# LM399.net
KiCad netlist of a schematic drawn in Altium Designer
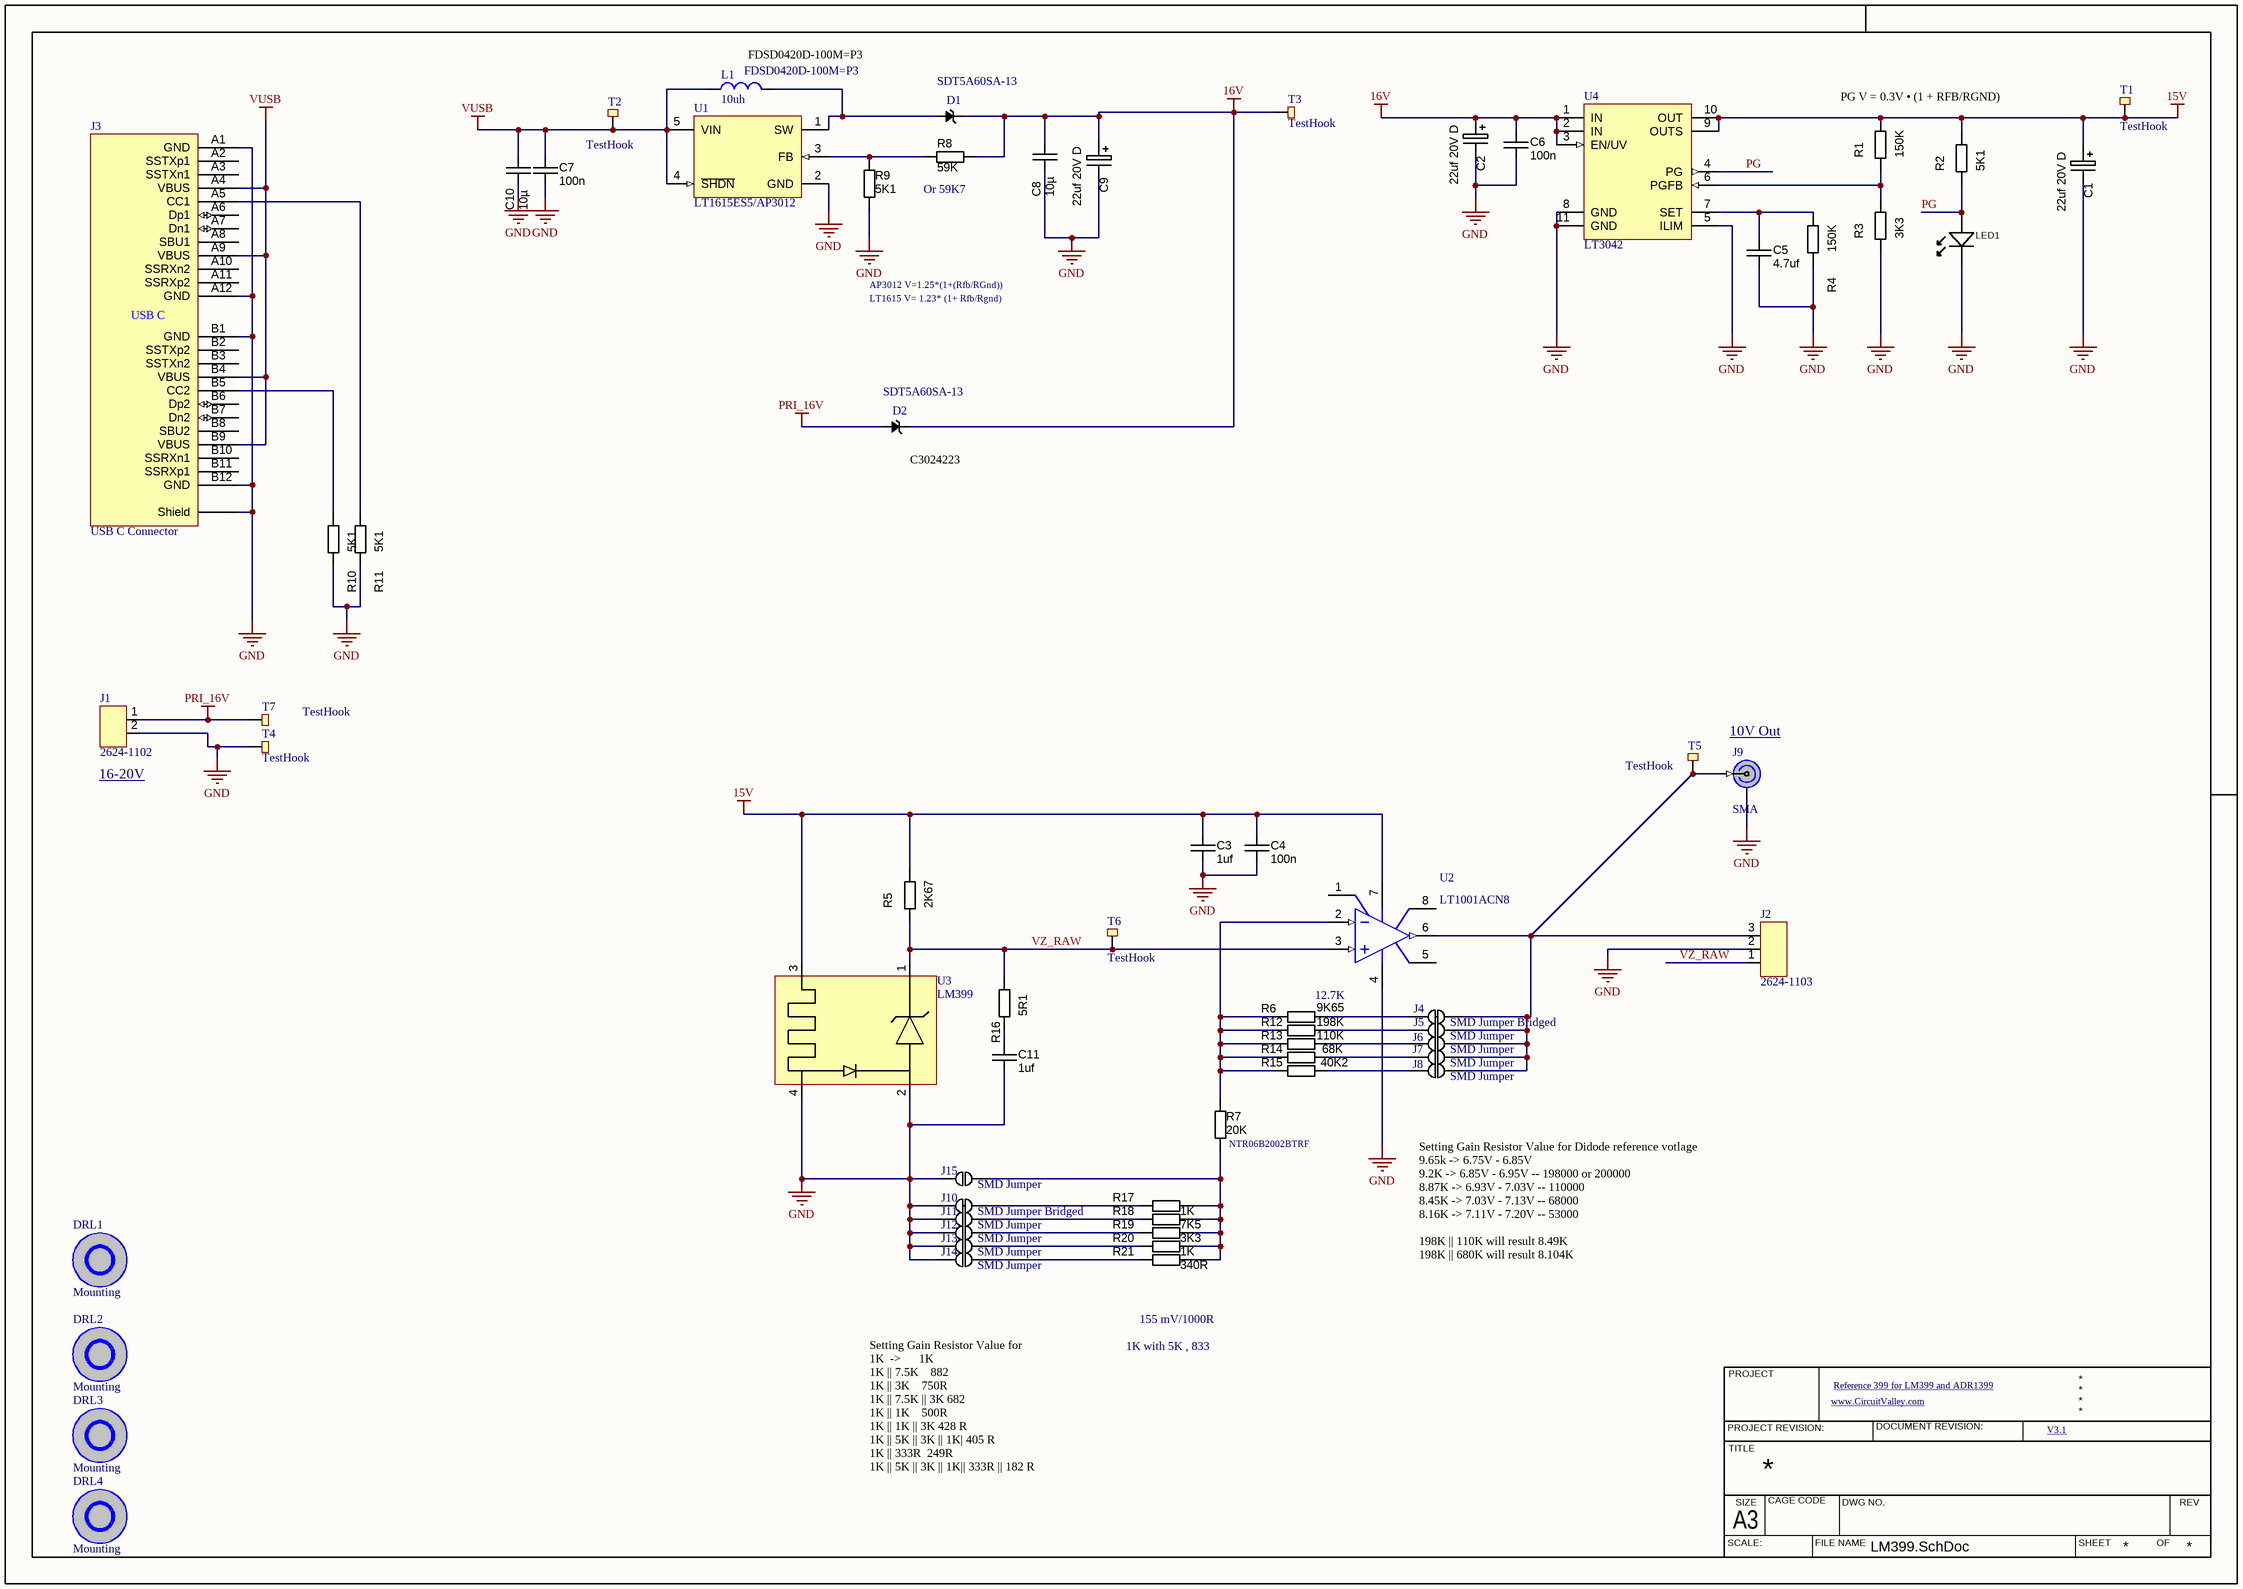
[diagram p0: LM399.SchDoc]

(export (version "E")
  (design (tool "Eeschema 10.0.6"))
  (components
    (comp (ref "C1")
      (value "22uf 20V D")
      (footprint "CAPMP7343X310N")
      (description "Capacitor SMD Tant 330uF 20% 6V3 2917")
      (fields
        (field (name "TOLERANCE") "±20%")
        (field (name "MANUFACTURER PART NUMBER") "T520D337M006ATE015")
      )
      (libsource (lib "PBL - Capacitors") (part "CAPT_330u_2917_6V3"))
    )
    (comp (ref "C2")
      (value "22uf 20V D")
      (footprint "CAPMP7343X310N")
      (description "Capacitor SMD Tant 330uF 20% 6V3 2917")
      (fields
        (field (name "TOLERANCE") "±20%")
        (field (name "MANUFACTURER PART NUMBER") "T520D337M006ATE015")
      )
      (libsource (lib "PBL - Capacitors") (part "CAPT_330u_2917_6V3"))
    )
    (comp (ref "C3")
      (value "1uf")
      (footprint "CAPC1608N")
      (description "Capacitor SMD Cer 1nF 10% 100V X7R 0603")
      (fields (field (name "TOLERANCE") "±10%") (field (name "Comment") "approved sub OK"))
      (libsource (lib "PBL - Capacitors") (part "CAPC_1n_0603_100V"))
    )
    (comp (ref "C4")
      (value "100n")
      (footprint "CAPC1608N")
      (description "Capacitor SMD Cer 1nF 10% 100V X7R 0603")
      (fields (field (name "TOLERANCE") "±10%") (field (name "Comment") "approved sub OK"))
      (libsource (lib "PBL - Capacitors") (part "CAPC_1n_0603_100V"))
    )
    (comp (ref "C5")
      (value "4.7uf")
      (footprint "CAPC1608N")
      (description "Capacitor SMD Cer 1nF 10% 100V X7R 0603")
      (fields (field (name "TOLERANCE") "±10%") (field (name "Comment") "approved sub OK"))
      (libsource (lib "PBL - Capacitors") (part "CAPC_1n_0603_100V"))
    )
    (comp (ref "C6")
      (value "100n")
      (footprint "CAPC1608N")
      (description "Capacitor SMD Cer 1nF 10% 100V X7R 0603")
      (fields (field (name "TOLERANCE") "±10%") (field (name "Comment") "approved sub OK"))
      (libsource (lib "PBL - Capacitors") (part "CAPC_1n_0603_100V"))
    )
    (comp (ref "C7")
      (value "100n")
      (footprint "CAPC1608N")
      (description "Capacitor SMD Cer 1nF 10% 100V X7R 0603")
      (fields (field (name "TOLERANCE") "±10%") (field (name "Comment") "approved sub OK"))
      (libsource (lib "PBL - Capacitors") (part "CAPC_1n_0603_100V"))
    )
    (comp (ref "C8")
      (value "10µ")
      (footprint "CAPC3225N")
      (description "Capacitor SMD Cer 10uF 20% 16V X5R 1210")
      (fields (field (name "TOLERANCE") "±20%"))
      (libsource (lib "PBL - Capacitors") (part "CAPC_10u_1210_50V"))
    )
    (comp (ref "C9")
      (value "22uf 20V D")
      (footprint "CAPMP7343X310N")
      (description "Capacitor SMD Tant 330uF 20% 6V3 2917")
      (fields
        (field (name "TOLERANCE") "±20%")
        (field (name "MANUFACTURER PART NUMBER") "T520D337M006ATE015")
      )
      (libsource (lib "PBL - Capacitors") (part "CAPT_330u_2917_6V3"))
    )
    (comp (ref "C10")
      (value "10µ")
      (footprint "CAPC3225N")
      (description "Capacitor SMD Cer 10uF 20% 16V X5R 1210")
      (fields (field (name "TOLERANCE") "±20%"))
      (libsource (lib "PBL - Capacitors") (part "CAPC_10u_1210_50V"))
    )
    (comp (ref "C11")
      (value "1uf")
      (footprint "CAPC1608N")
      (description "Capacitor SMD Cer 1nF 10% 100V X7R 0603")
      (fields (field (name "TOLERANCE") "±10%") (field (name "Comment") "approved sub OK"))
      (libsource (lib "PBL - Capacitors") (part "CAPC_1n_0603_100V"))
    )
    (comp (ref "D1")
      (value "SDT5A60SA-13")
      (footprint "DO-214AC")
      (libsource (lib "cvlib") (part "Schottky_diode"))
    )
    (comp (ref "D2")
      (value "SDT5A60SA-13")
      (footprint "DO-214AC")
      (libsource (lib "cvlib") (part "Schottky_diode"))
    )
    (comp (ref "DRL1")
      (value "Mounting")
      (footprint "NO_COPPER_NOMASK_2m75_6m2")
      (description "Mounting Hole")
      (libsource (lib "cvlib") (part "Mountinghole"))
    )
    (comp (ref "DRL2")
      (value "Mounting")
      (footprint "NO_COPPER_NOMASK_2m75_6m2")
      (description "Mounting Hole")
      (libsource (lib "cvlib") (part "Mountinghole"))
    )
    (comp (ref "DRL3")
      (value "Mounting")
      (footprint "NO_COPPER_NOMASK_2m75_6m2")
      (description "Mounting Hole")
      (libsource (lib "cvlib") (part "Mountinghole"))
    )
    (comp (ref "DRL4")
      (value "Mounting")
      (footprint "NO_COPPER_NOMASK_2m75_6m2")
      (description "Mounting Hole")
      (libsource (lib "cvlib") (part "Mountinghole"))
    )
    (comp (ref "J1") (value "2624-1102") (footprint "2624-1102") (libsource (lib "cvlib") (part "2624-1102")))
    (comp (ref "J2") (value "2624-1103") (footprint "2624-1103") (libsource (lib "cvlib") (part "2624-1103")))
    (comp (ref "J3")
      (value "USB C Connector")
      (footprint "UT11113-11602-7H")
      (description "USB C connector")
      (libsource (lib "cvlib") (part "USB_C"))
    )
    (comp (ref "J4")
      (value "SMD Jumper Bridged")
      (footprint "SMD_Jumper_bridge")
      (description "SMD Jumper")
      (libsource (lib "cvlib") (part "SMD_Jumper_Bridged"))
    )
    (comp (ref "J5")
      (value "SMD Jumper")
      (footprint "SMD_Jumper")
      (libsource (lib "cvlib") (part "SMD_Jumper"))
    )
    (comp (ref "J6")
      (value "SMD Jumper")
      (footprint "SMD_Jumper")
      (libsource (lib "cvlib") (part "SMD_Jumper"))
    )
    (comp (ref "J7")
      (value "SMD Jumper")
      (footprint "SMD_Jumper")
      (libsource (lib "cvlib") (part "SMD_Jumper"))
    )
    (comp (ref "J8")
      (value "SMD Jumper")
      (footprint "SMD_Jumper")
      (libsource (lib "cvlib") (part "SMD_Jumper"))
    )
    (comp (ref "J9")
      (value "SMA")
      (footprint "SMA_Connector")
      (libsource (lib "cvlib") (part "SMA Connector"))
    )
    (comp (ref "J10")
      (value "SMD Jumper Bridged")
      (footprint "SMD_Jumper_bridge")
      (description "SMD Jumper")
      (libsource (lib "cvlib") (part "SMD_Jumper_Bridged"))
    )
    (comp (ref "J11")
      (value "SMD Jumper")
      (footprint "SMD_Jumper")
      (libsource (lib "cvlib") (part "SMD_Jumper"))
    )
    (comp (ref "J12")
      (value "SMD Jumper")
      (footprint "SMD_Jumper")
      (libsource (lib "cvlib") (part "SMD_Jumper"))
    )
    (comp (ref "J13")
      (value "SMD Jumper")
      (footprint "SMD_Jumper")
      (libsource (lib "cvlib") (part "SMD_Jumper"))
    )
    (comp (ref "J14")
      (value "SMD Jumper")
      (footprint "SMD_Jumper")
      (libsource (lib "cvlib") (part "SMD_Jumper"))
    )
    (comp (ref "J15")
      (value "SMD Jumper")
      (footprint "SMD_Jumper")
      (libsource (lib "cvlib") (part "SMD_Jumper"))
    )
    (comp (ref "L1")
      (value "10uh")
      (footprint "FDSD0420-H-2R2M")
      (fields (field (name "ALTIUM_VALUE") "FDSD0420D-100M=P3"))
      (libsource (lib "cvlib") (part "inductor_smd"))
    )
    (comp (ref "LED1")
      (value "~")
      (footprint "LED-0805-K")
      (description "LED, 0805 SMD, Green")
      (libsource (lib "PBL - Light Sources") (part "LED_SMD_Green_0805"))
    )
    (comp (ref "R1")
      (value "150K")
      (footprint "RESC1608N")
      (description "Resistor, SMD chip")
      (fields (field (name "TOLERANCE") "±5%") (field (name "Comment") "RES_NL_0603"))
      (libsource (lib "PBL - Resistors") (part "RES_NL_0603"))
    )
    (comp (ref "R2")
      (value "5K1")
      (footprint "RESC1608N")
      (description "Resistor, SMD chip")
      (fields (field (name "TOLERANCE") "±5%") (field (name "Comment") "RES_NL_0603"))
      (libsource (lib "PBL - Resistors") (part "RES_NL_0603"))
    )
    (comp (ref "R3")
      (value "3K3")
      (footprint "RESC1608N")
      (description "Resistor, SMD chip")
      (fields (field (name "TOLERANCE") "±5%") (field (name "Comment") "RES_NL_0603"))
      (libsource (lib "PBL - Resistors") (part "RES_NL_0603"))
    )
    (comp (ref "R4")
      (value "150K")
      (footprint "RESC1608N")
      (description "Resistor, SMD chip")
      (fields (field (name "TOLERANCE") "±5%") (field (name "Comment") "RES_NL_0603"))
      (libsource (lib "PBL - Resistors") (part "RES_NL_0603"))
    )
    (comp (ref "R5")
      (value "2K67")
      (footprint "RESC1608N")
      (description "Resistor, SMD chip")
      (fields (field (name "TOLERANCE") "±5%") (field (name "Comment") "RES_NL_0603"))
      (libsource (lib "PBL - Resistors") (part "RES_NL_0603"))
    )
    (comp (ref "R6")
      (value "9K65")
      (footprint "RESC1608N")
      (description "Resistor, SMD chip")
      (fields (field (name "TOLERANCE") "±5%") (field (name "Comment") "RES_NL_0603"))
      (libsource (lib "") (part "RES_NL_0603_1"))
    )
    (comp (ref "R7")
      (value "20K")
      (footprint "RESC1608N")
      (description "Resistor, SMD chip")
      (fields (field (name "TOLERANCE") "±5%") (field (name "Comment") "RES_NL_0603"))
      (libsource (lib "PBL - Resistors") (part "RES_NL_0603"))
    )
    (comp (ref "R8")
      (value "59K")
      (footprint "RESC1608N")
      (description "Resistor, SMD chip")
      (fields (field (name "TOLERANCE") "±5%") (field (name "Comment") "RES_NL_0603"))
      (libsource (lib "") (part "RES_NL_0603_1"))
    )
    (comp (ref "R9")
      (value "5K1")
      (footprint "RESC1608N")
      (description "Resistor, SMD chip")
      (fields (field (name "TOLERANCE") "±5%") (field (name "Comment") "RES_NL_0603"))
      (libsource (lib "") (part "RES_NL_0603_3"))
    )
    (comp (ref "R10")
      (value "5K1")
      (footprint "RESC1608N")
      (description "Resistor, SMD chip")
      (fields (field (name "TOLERANCE") "±5%") (field (name "Comment") "RES_NL_0603"))
      (libsource (lib "PBL - Resistors") (part "RES_NL_0603"))
    )
    (comp (ref "R11")
      (value "5K1")
      (footprint "RESC1608N")
      (description "Resistor, SMD chip")
      (fields (field (name "TOLERANCE") "±5%") (field (name "Comment") "RES_NL_0603"))
      (libsource (lib "PBL - Resistors") (part "RES_NL_0603"))
    )
    (comp (ref "R12")
      (value "198K")
      (footprint "RESC1608N")
      (description "Resistor, SMD chip")
      (fields (field (name "TOLERANCE") "±5%") (field (name "Comment") "RES_NL_0603"))
      (libsource (lib "") (part "RES_NL_0603_1"))
    )
    (comp (ref "R13")
      (value "110K")
      (footprint "RESC1608N")
      (description "Resistor, SMD chip")
      (fields (field (name "TOLERANCE") "±5%") (field (name "Comment") "RES_NL_0603"))
      (libsource (lib "") (part "RES_NL_0603_1"))
    )
    (comp (ref "R14")
      (value "68K")
      (footprint "RESC1608N")
      (description "Resistor, SMD chip")
      (fields (field (name "TOLERANCE") "±5%") (field (name "Comment") "RES_NL_0603"))
      (libsource (lib "") (part "RES_NL_0603_1"))
    )
    (comp (ref "R15")
      (value "40K2")
      (footprint "RESC1608N")
      (description "Resistor, SMD chip")
      (fields (field (name "TOLERANCE") "±5%") (field (name "Comment") "RES_NL_0603"))
      (libsource (lib "") (part "RES_NL_0603_1"))
    )
    (comp (ref "R16")
      (value "5R1")
      (footprint "RESC1608N")
      (description "Resistor, SMD chip")
      (fields (field (name "TOLERANCE") "±5%") (field (name "Comment") "RES_NL_0603"))
      (libsource (lib "PBL - Resistors") (part "RES_NL_0603"))
    )
    (comp (ref "R17")
      (value "1K")
      (footprint "RESC1608N")
      (description "Resistor, SMD chip")
      (fields (field (name "TOLERANCE") "±5%") (field (name "Comment") "RES_NL_0603"))
      (libsource (lib "") (part "RES_NL_0603_2"))
    )
    (comp (ref "R18")
      (value "7K5")
      (footprint "RESC1608N")
      (description "Resistor, SMD chip")
      (fields (field (name "TOLERANCE") "±5%") (field (name "Comment") "RES_NL_0603"))
      (libsource (lib "") (part "RES_NL_0603_2"))
    )
    (comp (ref "R19")
      (value "3K3")
      (footprint "RESC1608N")
      (description "Resistor, SMD chip")
      (fields (field (name "TOLERANCE") "±5%") (field (name "Comment") "RES_NL_0603"))
      (libsource (lib "") (part "RES_NL_0603_2"))
    )
    (comp (ref "R20")
      (value "1K")
      (footprint "RESC1608N")
      (description "Resistor, SMD chip")
      (fields (field (name "TOLERANCE") "±5%") (field (name "Comment") "RES_NL_0603"))
      (libsource (lib "") (part "RES_NL_0603_2"))
    )
    (comp (ref "R21")
      (value "340R")
      (footprint "RESC1608N")
      (description "Resistor, SMD chip")
      (fields (field (name "TOLERANCE") "±5%") (field (name "Comment") "RES_NL_0603"))
      (libsource (lib "") (part "RES_NL_0603_2"))
    )
    (comp (ref "T1")
      (value "TestHook")
      (footprint "Test_PAD_0851-0-15-20-82-14-11-0")
      (libsource (lib "cvlib") (part "TestHook"))
    )
    (comp (ref "T2")
      (value "TestHook")
      (footprint "Test_PAD_0851-0-15-20-82-14-11-0")
      (libsource (lib "cvlib") (part "TestHook"))
    )
    (comp (ref "T3")
      (value "TestHook")
      (footprint "Test_PAD_0851-0-15-20-82-14-11-0")
      (libsource (lib "") (part "TestHook_1"))
    )
    (comp (ref "T4")
      (value "TestHook")
      (footprint "Test_PAD_0851-0-15-20-82-14-11-0")
      (libsource (lib "") (part "TestHook_1"))
    )
    (comp (ref "T5")
      (value "TestHook")
      (footprint "Test_PAD_0851-0-15-20-82-14-11-0")
      (libsource (lib "cvlib") (part "TestHook"))
    )
    (comp (ref "T6")
      (value "TestHook")
      (footprint "Test_PAD_0851-0-15-20-82-14-11-0")
      (libsource (lib "cvlib") (part "TestHook"))
    )
    (comp (ref "T7")
      (value "TestHook")
      (footprint "Test_PAD_0851-0-15-20-82-14-11-0")
      (libsource (lib "") (part "TestHook_1"))
    )
    (comp (ref "U1")
      (value "LT1615ES5/AP3012")
      (footprint "SOT23-5")
      (description "Boost Conveter")
      (libsource (lib "cvlib") (part "AP3012"))
    )
    (comp (ref "U2")
      (value "LT1001ACN8")
      (footprint "N8")
      (description "General Purpose, High Precision Op Amp")
      (fields (field (name "PUBLISHER") "Altium Limited"))
      (libsource (lib "LT Operational Amplifier") (part "LT1001ACN8"))
    )
    (comp (ref "U3") (value "LM399") (footprint "TO-46") (libsource (lib "cvlib") (part "LM399")))
    (comp (ref "U4")
      (value "LT3042")
      (footprint "MSOP10")
      (description "Low noise Linear Regulator")
      (libsource (lib "cvlib") (part "LT3042"))
    )
  )
  (nets
    (net (code "1") (name "/PG") (class "Default")
      (node (ref "LED1") (pin "A") (pinfunction "A_A") (pintype "passive"))
      (node (ref "R2") (pin "2") (pinfunction "2_2") (pintype "passive"))
      (node (ref "U4") (pin "4") (pinfunction "PG_4") (pintype "output"))
    )
    (net (code "2") (name "/VZ_RAW") (class "Default")
      (node (ref "J2") (pin "1") (pintype "passive"))
      (node (ref "R16") (pin "1") (pinfunction "1_1") (pintype "passive"))
      (node (ref "R5") (pin "2") (pinfunction "2_2") (pintype "passive"))
      (node (ref "T6") (pin "1") (pinfunction "TP_1") (pintype "power_in"))
      (node (ref "U2") (pin "3") (pinfunction "IN+_3") (pintype "input"))
      (node (ref "U3") (pin "1") (pinfunction "D1_1") (pintype "passive"))
    )
    (net (code "3") (name "15V") (class "Default")
      (node (ref "C1") (pin "1") (pintype "passive"))
      (node (ref "C3") (pin "1") (pintype "passive"))
      (node (ref "C4") (pin "1") (pintype "passive"))
      (node (ref "R1") (pin "1") (pinfunction "1_1") (pintype "passive"))
      (node (ref "R2") (pin "1") (pinfunction "1_1") (pintype "passive"))
      (node (ref "R5") (pin "1") (pinfunction "1_1") (pintype "passive"))
      (node (ref "T1") (pin "1") (pinfunction "TP_1") (pintype "power_in"))
      (node (ref "U2") (pin "7") (pinfunction "V+_7") (pintype "power_in"))
      (node (ref "U3") (pin "3") (pinfunction "H1_3") (pintype "passive"))
      (node (ref "U4") (pin "10") (pinfunction "OUT_10") (pintype "power_in"))
      (node (ref "U4") (pin "9") (pinfunction "OUTS_9") (pintype "passive"))
    )
    (net (code "4") (name "16V") (class "Default")
      (node (ref "C2") (pin "1") (pintype "passive"))
      (node (ref "C6") (pin "1") (pintype "passive"))
      (node (ref "C8") (pin "1") (pintype "passive"))
      (node (ref "C9") (pin "1") (pintype "passive"))
      (node (ref "D1") (pin "2") (pinfunction "2_2") (pintype "passive"))
      (node (ref "D2") (pin "2") (pinfunction "2_2") (pintype "passive"))
      (node (ref "R8") (pin "2") (pinfunction "2_2") (pintype "passive"))
      (node (ref "T3") (pin "1") (pinfunction "TP_1") (pintype "power_in"))
      (node (ref "U4") (pin "1") (pinfunction "IN_1") (pintype "power_in"))
      (node (ref "U4") (pin "2") (pinfunction "IN_2") (pintype "power_in"))
      (node (ref "U4") (pin "3") (pinfunction "EN/UV_3") (pintype "input"))
    )
    (net (code "5") (name "GND") (class "Default")
      (node (ref "C1") (pin "2") (pintype "passive"))
      (node (ref "C10") (pin "2") (pintype "passive"))
      (node (ref "C11") (pin "2") (pintype "passive"))
      (node (ref "C2") (pin "2") (pintype "passive"))
      (node (ref "C3") (pin "2") (pintype "passive"))
      (node (ref "C4") (pin "2") (pintype "passive"))
      (node (ref "C5") (pin "2") (pintype "passive"))
      (node (ref "C6") (pin "2") (pintype "passive"))
      (node (ref "C7") (pin "2") (pintype "passive"))
      (node (ref "C8") (pin "2") (pintype "passive"))
      (node (ref "C9") (pin "2") (pintype "passive"))
      (node (ref "J1") (pin "2") (pinfunction "PW_2") (pintype "passive"))
      (node (ref "J10") (pin "2") (pinfunction "2_2") (pintype "passive"))
      (node (ref "J11") (pin "2") (pinfunction "2_2") (pintype "passive"))
      (node (ref "J12") (pin "2") (pinfunction "2_2") (pintype "passive"))
      (node (ref "J13") (pin "2") (pinfunction "2_2") (pintype "passive"))
      (node (ref "J14") (pin "2") (pinfunction "2_2") (pintype "passive"))
      (node (ref "J15") (pin "2") (pinfunction "2_2") (pintype "passive"))
      (node (ref "J2") (pin "2") (pintype "passive"))
      (node (ref "J3") (pin "0") (pinfunction "Shield_0") (pintype "power_in"))
      (node (ref "J3") (pin "A1") (pinfunction "GND_A1") (pintype "power_in"))
      (node (ref "J3") (pin "A12") (pinfunction "GND_A12") (pintype "power_in"))
      (node (ref "J3") (pin "B1") (pinfunction "GND_B1") (pintype "power_in"))
      (node (ref "J3") (pin "B12") (pinfunction "GND_B12") (pintype "power_in"))
      (node (ref "J9") (pin "2") (pinfunction "2_2") (pintype "passive"))
      (node (ref "LED1") (pin "K") (pinfunction "K_K") (pintype "passive"))
      (node (ref "R10") (pin "2") (pinfunction "2_2") (pintype "passive"))
      (node (ref "R11") (pin "2") (pinfunction "2_2") (pintype "passive"))
      (node (ref "R3") (pin "2") (pinfunction "2_2") (pintype "passive"))
      (node (ref "R4") (pin "2") (pinfunction "2_2") (pintype "passive"))
      (node (ref "R9") (pin "1") (pinfunction "1_1") (pintype "passive"))
      (node (ref "T4") (pin "1") (pinfunction "TP_1") (pintype "power_in"))
      (node (ref "U1") (pin "2") (pinfunction "GND_2") (pintype "power_in"))
      (node (ref "U2") (pin "4") (pinfunction "V-_4") (pintype "power_in"))
      (node (ref "U3") (pin "2") (pinfunction "D2_2") (pintype "passive"))
      (node (ref "U3") (pin "4") (pinfunction "H2_4") (pintype "passive"))
      (node (ref "U4") (pin "11") (pinfunction "GND_11") (pintype "passive"))
      (node (ref "U4") (pin "5") (pinfunction "ILIM_5") (pintype "passive"))
      (node (ref "U4") (pin "8") (pinfunction "GND_8") (pintype "passive"))
    )
    (net (code "6") (name "Net-(C11-Pad1)") (class "Default")
      (node (ref "C11") (pin "1") (pintype "passive"))
      (node (ref "R16") (pin "2") (pinfunction "2_2") (pintype "passive"))
    )
    (net (code "7") (name "Net-(J3-CC1)") (class "Default")
      (node (ref "J3") (pin "A5") (pinfunction "CC1_A5") (pintype "power_in"))
      (node (ref "R11") (pin "1") (pinfunction "1_1") (pintype "passive"))
    )
    (net (code "8") (name "Net-(J3-CC2)") (class "Default")
      (node (ref "J3") (pin "B5") (pinfunction "CC2_B5") (pintype "power_in"))
      (node (ref "R10") (pin "1") (pinfunction "1_1") (pintype "passive"))
    )
    (net (code "9") (name "Net-(J4-Pad2)") (class "Default")
      (node (ref "J4") (pin "2") (pinfunction "2_2") (pintype "passive"))
      (node (ref "R6") (pin "2") (pinfunction "2_2") (pintype "passive"))
    )
    (net (code "10") (name "Net-(J5-Pad2)") (class "Default")
      (node (ref "J5") (pin "2") (pinfunction "2_2") (pintype "passive"))
      (node (ref "R12") (pin "2") (pinfunction "2_2") (pintype "passive"))
    )
    (net (code "11") (name "Net-(J6-Pad2)") (class "Default")
      (node (ref "J6") (pin "2") (pinfunction "2_2") (pintype "passive"))
      (node (ref "R13") (pin "2") (pinfunction "2_2") (pintype "passive"))
    )
    (net (code "12") (name "Net-(J7-Pad2)") (class "Default")
      (node (ref "J7") (pin "2") (pinfunction "2_2") (pintype "passive"))
      (node (ref "R14") (pin "2") (pinfunction "2_2") (pintype "passive"))
    )
    (net (code "13") (name "Net-(J8-Pad2)") (class "Default")
      (node (ref "J8") (pin "2") (pinfunction "2_2") (pintype "passive"))
      (node (ref "R15") (pin "2") (pinfunction "2_2") (pintype "passive"))
    )
    (net (code "14") (name "Net-(J10-Pad1)") (class "Default")
      (node (ref "J10") (pin "1") (pinfunction "1_1") (pintype "passive"))
      (node (ref "R17") (pin "2") (pinfunction "2_2") (pintype "passive"))
    )
    (net (code "15") (name "Net-(J11-Pad1)") (class "Default")
      (node (ref "J11") (pin "1") (pinfunction "1_1") (pintype "passive"))
      (node (ref "R18") (pin "2") (pinfunction "2_2") (pintype "passive"))
    )
    (net (code "16") (name "Net-(J12-Pad1)") (class "Default")
      (node (ref "J12") (pin "1") (pinfunction "1_1") (pintype "passive"))
      (node (ref "R19") (pin "2") (pinfunction "2_2") (pintype "passive"))
    )
    (net (code "17") (name "Net-(J13-Pad1)") (class "Default")
      (node (ref "J13") (pin "1") (pinfunction "1_1") (pintype "passive"))
      (node (ref "R20") (pin "2") (pinfunction "2_2") (pintype "passive"))
    )
    (net (code "18") (name "Net-(J14-Pad1)") (class "Default")
      (node (ref "J14") (pin "1") (pinfunction "1_1") (pintype "passive"))
      (node (ref "R21") (pin "2") (pinfunction "2_2") (pintype "passive"))
    )
    (net (code "19") (name "Net-(J15-Pad1)") (class "Default")
      (node (ref "J15") (pin "1") (pinfunction "1_1") (pintype "passive"))
      (node (ref "R17") (pin "1") (pinfunction "1_1") (pintype "passive"))
      (node (ref "R18") (pin "1") (pinfunction "1_1") (pintype "passive"))
      (node (ref "R19") (pin "1") (pinfunction "1_1") (pintype "passive"))
      (node (ref "R20") (pin "1") (pinfunction "1_1") (pintype "passive"))
      (node (ref "R21") (pin "1") (pinfunction "1_1") (pintype "passive"))
      (node (ref "R7") (pin "2") (pinfunction "2_2") (pintype "passive"))
    )
    (net (code "20") (name "Net-(T5-TP)") (class "Default")
      (node (ref "J2") (pin "3") (pintype "passive"))
      (node (ref "J4") (pin "1") (pinfunction "1_1") (pintype "passive"))
      (node (ref "J5") (pin "1") (pinfunction "1_1") (pintype "passive"))
      (node (ref "J6") (pin "1") (pinfunction "1_1") (pintype "passive"))
      (node (ref "J7") (pin "1") (pinfunction "1_1") (pintype "passive"))
      (node (ref "J8") (pin "1") (pinfunction "1_1") (pintype "passive"))
      (node (ref "J9") (pin "1") (pinfunction "1_1") (pintype "input"))
      (node (ref "T5") (pin "1") (pinfunction "TP_1") (pintype "power_in"))
      (node (ref "U2") (pin "6") (pinfunction "OUT_6") (pintype "output"))
    )
    (net (code "21") (name "Net-(U1-FB)") (class "Default")
      (node (ref "R8") (pin "1") (pinfunction "1_1") (pintype "passive"))
      (node (ref "R9") (pin "2") (pinfunction "2_2") (pintype "passive"))
      (node (ref "U1") (pin "3") (pinfunction "FB_3") (pintype "input"))
    )
    (net (code "22") (name "Net-(U1-SW)") (class "Default")
      (node (ref "D1") (pin "1") (pinfunction "1_1") (pintype "passive"))
      (node (ref "L1") (pin "2") (pinfunction "2_2") (pintype "passive"))
      (node (ref "U1") (pin "1") (pinfunction "SW_1") (pintype "power_in"))
    )
    (net (code "23") (name "Net-(U2-IN-)") (class "Default")
      (node (ref "R12") (pin "1") (pinfunction "1_1") (pintype "passive"))
      (node (ref "R13") (pin "1") (pinfunction "1_1") (pintype "passive"))
      (node (ref "R14") (pin "1") (pinfunction "1_1") (pintype "passive"))
      (node (ref "R15") (pin "1") (pinfunction "1_1") (pintype "passive"))
      (node (ref "R6") (pin "1") (pinfunction "1_1") (pintype "passive"))
      (node (ref "R7") (pin "1") (pinfunction "1_1") (pintype "passive"))
      (node (ref "U2") (pin "2") (pinfunction "IN-_2") (pintype "input"))
    )
    (net (code "24") (name "Net-(U4-PGFB)") (class "Default")
      (node (ref "R1") (pin "2") (pinfunction "2_2") (pintype "passive"))
      (node (ref "R3") (pin "1") (pinfunction "1_1") (pintype "passive"))
      (node (ref "U4") (pin "6") (pinfunction "PGFB_6") (pintype "input"))
    )
    (net (code "25") (name "Net-(U4-SET)") (class "Default")
      (node (ref "C5") (pin "1") (pintype "passive"))
      (node (ref "R4") (pin "1") (pinfunction "1_1") (pintype "passive"))
      (node (ref "U4") (pin "7") (pinfunction "SET_7") (pintype "passive"))
    )
    (net (code "26") (name "PRI_16V") (class "Default")
      (node (ref "D2") (pin "1") (pinfunction "1_1") (pintype "passive"))
      (node (ref "J1") (pin "1") (pinfunction "PW_1") (pintype "passive"))
      (node (ref "T7") (pin "1") (pinfunction "TP_1") (pintype "power_in"))
    )
    (net (code "27") (name "VUSB") (class "Default")
      (node (ref "C10") (pin "1") (pintype "passive"))
      (node (ref "C7") (pin "1") (pintype "passive"))
      (node (ref "J3") (pin "A4") (pinfunction "VBUS_A4") (pintype "power_in"))
      (node (ref "J3") (pin "A9") (pinfunction "VBUS_A9") (pintype "power_in"))
      (node (ref "J3") (pin "B4") (pinfunction "VBUS_B4") (pintype "power_in"))
      (node (ref "J3") (pin "B9") (pinfunction "VBUS_B9") (pintype "power_in"))
      (node (ref "L1") (pin "1") (pinfunction "1_1") (pintype "passive"))
      (node (ref "T2") (pin "1") (pinfunction "TP_1") (pintype "power_in"))
      (node (ref "U1") (pin "4") (pinfunction "~{SHDN}_4") (pintype "input"))
      (node (ref "U1") (pin "5") (pinfunction "VIN_5") (pintype "power_in"))
    )
    (net (code "28") (name "unconnected-(J3-Dn1-PadA7)") (class "Default")
      (node (ref "J3") (pin "A7") (pinfunction "Dn1_A7") (pintype "bidirectional"))
    )
    (net (code "29") (name "unconnected-(J3-Dn2-PadB7)") (class "Default")
      (node (ref "J3") (pin "B7") (pinfunction "Dn2_B7") (pintype "bidirectional"))
    )
    (net (code "30") (name "unconnected-(J3-Dp1-PadA6)") (class "Default")
      (node (ref "J3") (pin "A6") (pinfunction "Dp1_A6") (pintype "bidirectional"))
    )
    (net (code "31") (name "unconnected-(J3-Dp2-PadB6)") (class "Default")
      (node (ref "J3") (pin "B6") (pinfunction "Dp2_B6") (pintype "bidirectional"))
    )
    (net (code "32") (name "unconnected-(J3-SBU1-PadA8)") (class "Default")
      (node (ref "J3") (pin "A8") (pinfunction "SBU1_A8") (pintype "power_in"))
    )
    (net (code "33") (name "unconnected-(J3-SBU2-PadB8)") (class "Default")
      (node (ref "J3") (pin "B8") (pinfunction "SBU2_B8") (pintype "power_in"))
    )
    (net (code "34") (name "unconnected-(J3-SSRXn1-PadB10)") (class "Default")
      (node (ref "J3") (pin "B10") (pinfunction "SSRXn1_B10") (pintype "passive"))
    )
    (net (code "35") (name "unconnected-(J3-SSRXn2-PadA10)") (class "Default")
      (node (ref "J3") (pin "A10") (pinfunction "SSRXn2_A10") (pintype "passive"))
    )
    (net (code "36") (name "unconnected-(J3-SSRXp1-PadB11)") (class "Default")
      (node (ref "J3") (pin "B11") (pinfunction "SSRXp1_B11") (pintype "passive"))
    )
    (net (code "37") (name "unconnected-(J3-SSRXp2-PadA11)") (class "Default")
      (node (ref "J3") (pin "A11") (pinfunction "SSRXp2_A11") (pintype "passive"))
    )
    (net (code "38") (name "unconnected-(J3-SSTXn1-PadA3)") (class "Default")
      (node (ref "J3") (pin "A3") (pinfunction "SSTXn1_A3") (pintype "passive"))
    )
    (net (code "39") (name "unconnected-(J3-SSTXn2-PadB3)") (class "Default")
      (node (ref "J3") (pin "B3") (pinfunction "SSTXn2_B3") (pintype "passive"))
    )
    (net (code "40") (name "unconnected-(J3-SSTXp1-PadA2)") (class "Default")
      (node (ref "J3") (pin "A2") (pinfunction "SSTXp1_A2") (pintype "passive"))
    )
    (net (code "41") (name "unconnected-(J3-SSTXp2-PadB2)") (class "Default")
      (node (ref "J3") (pin "B2") (pinfunction "SSTXp2_B2") (pintype "passive"))
    )
    (net (code "42") (name "unconnected-(U2-NC-Pad5)") (class "Default")
      (node (ref "U2") (pin "5") (pinfunction "NC_5") (pintype "passive"))
    )
    (net (code "43") (name "unconnected-(U2-VOSTRIM-Pad1)") (class "Default")
      (node (ref "U2") (pin "1") (pinfunction "VOSTRIM_1") (pintype "passive"))
    )
    (net (code "44") (name "unconnected-(U2-VOSTRIM-Pad8)") (class "Default")
      (node (ref "U2") (pin "8") (pinfunction "VOSTRIM_8") (pintype "passive"))
    )
  )
)
